# msxbreakout_slim.net
KiCad netlist of a schematic drawn in Altium Designer
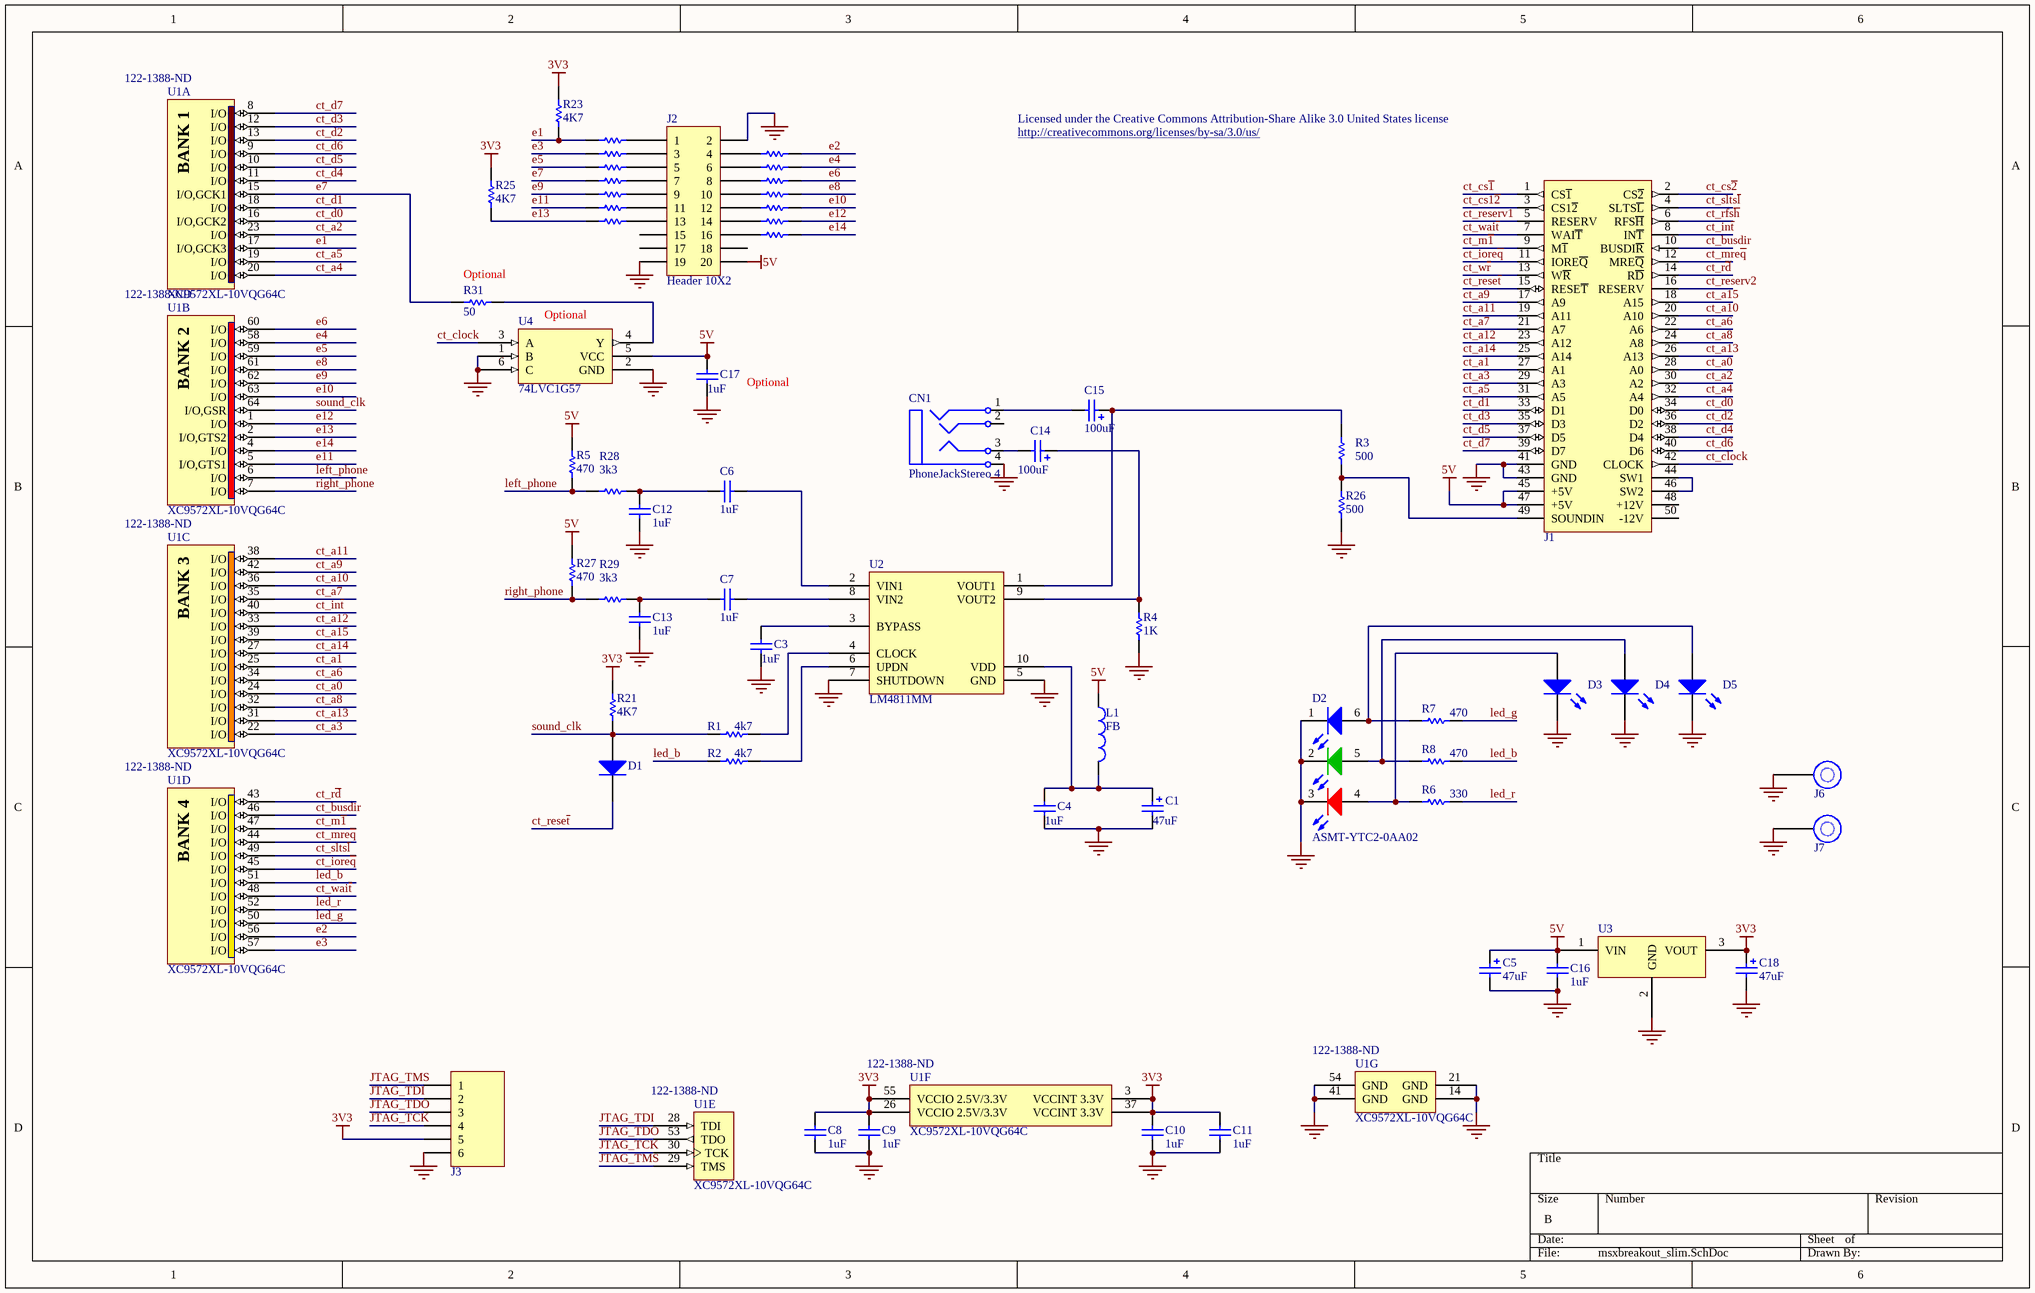
[diagram p0: msxbreakout_slim.SchDoc]

(export (version "E")
  (design (tool "Eeschema 10.0.6"))
  (components
    (comp (ref "C1")
      (value "47uF")
      (footprint "cap1210POL")
      (description "Polarized Capacitor")
      (fields (field (name "Comment") "Cap Pol1") (field (name "PUBLISHER") "Altium Limited"))
      (libsource (lib "msxarm") (part "Cap Pol1"))
    )
    (comp (ref "C3")
      (value "1uF")
      (footprint "cap0603")
      (description "Capacitor")
      (fields (field (name "Comment") "Cap") (field (name "PUBLISHER") "Altium Limited"))
      (libsource (lib "msxarm") (part "Cap"))
    )
    (comp (ref "C4")
      (value "1uF")
      (footprint "cap0603")
      (description "Capacitor")
      (fields (field (name "Comment") "Cap") (field (name "PUBLISHER") "Altium Limited"))
      (libsource (lib "msxarm") (part "Cap"))
    )
    (comp (ref "C5")
      (value "47uF")
      (footprint "cap1210POL")
      (description "Polarized Capacitor")
      (fields (field (name "Comment") "Cap Pol1") (field (name "PUBLISHER") "Altium Limited"))
      (libsource (lib "altium-import") (part "root_3_Cap Pol1_"))
    )
    (comp (ref "C6")
      (value "1uF")
      (footprint "cap0603")
      (description "Capacitor")
      (fields (field (name "Comment") "Cap") (field (name "PUBLISHER") "Altium Limited"))
      (libsource (lib "msxarm") (part "Cap"))
    )
    (comp (ref "C7")
      (value "1uF")
      (footprint "cap0603")
      (description "Capacitor")
      (fields (field (name "Comment") "Cap") (field (name "PUBLISHER") "Altium Limited"))
      (libsource (lib "msxarm") (part "Cap"))
    )
    (comp (ref "C8")
      (value "1uF")
      (footprint "cap0603")
      (description "Capacitor")
      (fields (field (name "Comment") "Cap") (field (name "PUBLISHER") "Altium Limited"))
      (libsource (lib "altium-import") (part "root_1_Cap_"))
    )
    (comp (ref "C9")
      (value "1uF")
      (footprint "cap0603")
      (description "Capacitor")
      (fields (field (name "Comment") "Cap") (field (name "PUBLISHER") "Altium Limited"))
      (libsource (lib "altium-import") (part "root_1_Cap_"))
    )
    (comp (ref "C10")
      (value "1uF")
      (footprint "cap0603")
      (description "Capacitor")
      (fields (field (name "Comment") "Cap") (field (name "PUBLISHER") "Altium Limited"))
      (libsource (lib "altium-import") (part "root_1_Cap_"))
    )
    (comp (ref "C11")
      (value "1uF")
      (footprint "cap0603")
      (description "Capacitor")
      (fields (field (name "Comment") "Cap") (field (name "PUBLISHER") "Altium Limited"))
      (libsource (lib "altium-import") (part "root_1_Cap_"))
    )
    (comp (ref "C12")
      (value "1uF")
      (footprint "cap0603")
      (description "Capacitor")
      (fields (field (name "Comment") "Cap") (field (name "PUBLISHER") "Altium Limited"))
      (libsource (lib "altium-import") (part "root_3_Cap_"))
    )
    (comp (ref "C13")
      (value "1uF")
      (footprint "cap0603")
      (description "Capacitor")
      (fields (field (name "Comment") "Cap") (field (name "PUBLISHER") "Altium Limited"))
      (libsource (lib "msxarm") (part "Cap"))
    )
    (comp (ref "C14")
      (value "100uF")
      (footprint "cap1210POL")
      (description "Polarized Capacitor")
      (fields (field (name "Comment") "Cap Pol1") (field (name "PUBLISHER") "Altium Limited"))
      (libsource (lib "msxarm") (part "Cap Pol1"))
    )
    (comp (ref "C15")
      (value "100uF")
      (footprint "cap1210POL")
      (description "Polarized Capacitor")
      (fields (field (name "Comment") "Cap Pol1") (field (name "PUBLISHER") "Altium Limited"))
      (libsource (lib "msxarm") (part "Cap Pol1"))
    )
    (comp (ref "C16")
      (value "1uF")
      (footprint "cap0603")
      (description "Capacitor")
      (fields (field (name "Comment") "Cap") (field (name "PUBLISHER") "Altium Limited"))
      (libsource (lib "msxarm") (part "Cap"))
    )
    (comp (ref "C17")
      (value "1uF")
      (footprint "cap0603")
      (description "Capacitor")
      (fields (field (name "Comment") "Cap") (field (name "PUBLISHER") "Altium Limited"))
      (libsource (lib "altium-import") (part "root_1_Cap_"))
    )
    (comp (ref "C18")
      (value "47uF")
      (footprint "cap1210POL")
      (description "Polarized Capacitor")
      (fields (field (name "Comment") "Cap Pol1") (field (name "PUBLISHER") "Altium Limited"))
      (libsource (lib "msxarm") (part "Cap Pol1"))
    )
    (comp (ref "CN1")
      (value "PhoneJackStereo 4")
      (footprint "SJ1-2503A")
      (libsource (lib "altium-import") (part "root_0_PhoneJackStereo4_"))
    )
    (comp (ref "D1")
      (value "Diode")
      (footprint "SOD323F")
      (description "Default Diode")
      (fields (field (name "PUBLISHER") "Altium Limited"))
      (libsource (lib "msxarm") (part "Diode"))
    )
    (comp (ref "D2")
      (value "ASMT-YTC2-0AA02")
      (footprint "ASMT-YTC2-0AA02")
      (description "Typical RED, GREEN, YELLOW, AMBER GaAs LED")
      (fields (field (name "PUBLISHER") "Altium Limited"))
      (libsource (lib "msxarm") (part "ASMT-YTC2-0AA02"))
    )
    (comp (ref "D3")
      (value "APA1606SURCK")
      (footprint "LED-0603_LAMP_RED")
      (description "1.6x0.6mm RIGHT ANGLE SMD CHIP LED LAMP, Hyper Red")
      (libsource (lib "altium-import") (part "root_3_APA1606SURCK_"))
    )
    (comp (ref "D4")
      (value "APA1606SURCK")
      (footprint "LED-0603_LAMP_GREEN")
      (description "1.6x0.6mm RIGHT ANGLE SMD CHIP LED LAMP, Hyper Red")
      (libsource (lib "altium-import") (part "root_3_APA1606SURCK_"))
    )
    (comp (ref "D5")
      (value "APA1606SURCK")
      (footprint "LED-0603_LAMP_BLUE")
      (description "1.6x0.6mm RIGHT ANGLE SMD CHIP LED LAMP, Hyper Red")
      (libsource (lib "altium-import") (part "root_3_APA1606SURCK_"))
    )
    (comp (ref "J1")
      (value "msxcart")
      (footprint "msxcart")
      (libsource (lib "altium-import") (part "root_0_msxcart_"))
    )
    (comp (ref "J2")
      (value "Header 10X2")
      (footprint "HDR2X10_90")
      (description "Header, 10-Pin, Dual row")
      (libsource (lib "altium-import") (part "root_0_Header 10X2_"))
    )
    (comp (ref "J3")
      (value "Header 1X6")
      (footprint "HDR1X6_90")
      (description "Header, 6-Pin, Single row")
      (libsource (lib "altium-import") (part "root_0_Header 1X6_"))
    )
    (comp (ref "J6")
      (value "MountHole")
      (footprint "MOUNTHOLE")
      (description "Mounting hole")
      (libsource (lib "msxarm") (part "MountHole"))
    )
    (comp (ref "J7")
      (value "MountHole")
      (footprint "MOUNTHOLE")
      (description "Mounting hole")
      (libsource (lib "msxarm") (part "MountHole"))
    )
    (comp (ref "L1")
      (value "FB")
      (footprint "ind1206")
      (description "Inductor")
      (fields (field (name "PUBLISHER") "Altium Limited"))
      (libsource (lib "altium-import") (part "root_3_Inductor_"))
    )
    (comp (ref "R1")
      (value "4k7")
      (footprint "res0603")
      (description "Resistor")
      (fields (field (name "Comment") "Res1") (field (name "PUBLISHER") "Altium Limited"))
      (libsource (lib "altium-import") (part "root_0_Res1_"))
    )
    (comp (ref "R2")
      (value "4k7")
      (footprint "msxbreakout:res0603")
      (description "Resistor")
      (fields (field (name "Comment") "Res1") (field (name "PUBLISHER") "Altium Limited"))
      (libsource (lib "altium-import") (part "root_0_Res1_"))
    )
    (comp (ref "R3")
      (value "500")
      (footprint "res0603")
      (description "Resistor")
      (fields (field (name "Comment") "Res1") (field (name "PUBLISHER") "Altium Limited"))
      (libsource (lib "altium-import") (part "root_1_Res1_"))
    )
    (comp (ref "R4")
      (value "1K")
      (footprint "res0603")
      (description "Resistor")
      (fields (field (name "Comment") "Res1") (field (name "PUBLISHER") "Altium Limited"))
      (libsource (lib "altium-import") (part "root_1_Res1_"))
    )
    (comp (ref "R5")
      (value "470")
      (footprint "msxbreakout:res0603")
      (description "Resistor")
      (fields (field (name "Comment") "Res1") (field (name "PUBLISHER") "Altium Limited"))
      (libsource (lib "altium-import") (part "root_1_Res1_"))
    )
    (comp (ref "R6")
      (value "330")
      (footprint "res0603")
      (description "Resistor")
      (fields (field (name "Comment") "Res1") (field (name "PUBLISHER") "Altium Limited"))
      (libsource (lib "altium-import") (part "root_0_Res1_"))
    )
    (comp (ref "R7")
      (value "470")
      (footprint "res0603")
      (description "Resistor")
      (fields (field (name "Comment") "Res1") (field (name "PUBLISHER") "Altium Limited"))
      (libsource (lib "altium-import") (part "root_0_Res1_"))
    )
    (comp (ref "R8")
      (value "470")
      (footprint "res0603")
      (description "Resistor")
      (fields (field (name "Comment") "Res1") (field (name "PUBLISHER") "Altium Limited"))
      (libsource (lib "altium-import") (part "root_0_Res1_"))
    )
    (comp (ref "R9")
      (value "Res1")
      (footprint "res0603")
      (description "Resistor")
      (fields (field (name "PUBLISHER") "Altium Limited"))
      (libsource (lib "altium-import") (part "root_0_Res1_"))
    )
    (comp (ref "R10")
      (value "Res1")
      (footprint "res0603")
      (description "Resistor")
      (fields (field (name "PUBLISHER") "Altium Limited"))
      (libsource (lib "altium-import") (part "root_0_Res1_"))
    )
    (comp (ref "R11")
      (value "Res1")
      (footprint "res0603")
      (description "Resistor")
      (fields (field (name "PUBLISHER") "Altium Limited"))
      (libsource (lib "altium-import") (part "root_0_Res1_"))
    )
    (comp (ref "R12")
      (value "Res1")
      (footprint "res0603")
      (description "Resistor")
      (fields (field (name "PUBLISHER") "Altium Limited"))
      (libsource (lib "altium-import") (part "root_0_Res1_"))
    )
    (comp (ref "R13")
      (value "Res1")
      (footprint "res0603")
      (description "Resistor")
      (fields (field (name "PUBLISHER") "Altium Limited"))
      (libsource (lib "altium-import") (part "root_0_Res1_"))
    )
    (comp (ref "R14")
      (value "Res1")
      (footprint "res0603")
      (description "Resistor")
      (fields (field (name "PUBLISHER") "Altium Limited"))
      (libsource (lib "altium-import") (part "root_0_Res1_"))
    )
    (comp (ref "R15")
      (value "Res1")
      (footprint "res0603")
      (description "Resistor")
      (fields (field (name "PUBLISHER") "Altium Limited"))
      (libsource (lib "altium-import") (part "root_0_Res1_"))
    )
    (comp (ref "R16")
      (value "Res1")
      (footprint "res0603")
      (description "Resistor")
      (fields (field (name "PUBLISHER") "Altium Limited"))
      (libsource (lib "altium-import") (part "root_0_Res1_"))
    )
    (comp (ref "R17")
      (value "Res1")
      (footprint "res0603")
      (description "Resistor")
      (fields (field (name "PUBLISHER") "Altium Limited"))
      (libsource (lib "altium-import") (part "root_0_Res1_"))
    )
    (comp (ref "R18")
      (value "Res1")
      (footprint "res0603")
      (description "Resistor")
      (fields (field (name "PUBLISHER") "Altium Limited"))
      (libsource (lib "altium-import") (part "root_0_Res1_"))
    )
    (comp (ref "R19")
      (value "Res1")
      (footprint "msxbreakout:res0603")
      (description "Resistor")
      (fields (field (name "PUBLISHER") "Altium Limited"))
      (libsource (lib "altium-import") (part "root_0_Res1_"))
    )
    (comp (ref "R20")
      (value "Res1")
      (footprint "res0603")
      (description "Resistor")
      (fields (field (name "PUBLISHER") "Altium Limited"))
      (libsource (lib "altium-import") (part "root_0_Res1_"))
    )
    (comp (ref "R21")
      (value "4K7")
      (footprint "msxbreakout:res0603")
      (description "Resistor")
      (fields (field (name "Comment") "Res1") (field (name "PUBLISHER") "Altium Limited"))
      (libsource (lib "altium-import") (part "root_1_Res1_"))
    )
    (comp (ref "R22")
      (value "Res1")
      (footprint "res0603")
      (description "Resistor")
      (fields (field (name "PUBLISHER") "Altium Limited"))
      (libsource (lib "altium-import") (part "root_0_Res1_"))
    )
    (comp (ref "R23")
      (value "4K7")
      (footprint "msxbreakout:res0603")
      (description "Resistor")
      (fields (field (name "Comment") "Res1") (field (name "PUBLISHER") "Altium Limited"))
      (libsource (lib "altium-import") (part "root_1_Res1_"))
    )
    (comp (ref "R24")
      (value "Res1")
      (footprint "res0603")
      (description "Resistor")
      (fields (field (name "PUBLISHER") "Altium Limited"))
      (libsource (lib "altium-import") (part "root_0_Res1_"))
    )
    (comp (ref "R25")
      (value "4K7")
      (footprint "res0603")
      (description "Resistor")
      (fields (field (name "Comment") "Res1") (field (name "PUBLISHER") "Altium Limited"))
      (libsource (lib "altium-import") (part "root_1_Res1_"))
    )
    (comp (ref "R26")
      (value "500")
      (footprint "res0603")
      (description "Resistor")
      (fields (field (name "Comment") "Res1") (field (name "PUBLISHER") "Altium Limited"))
      (libsource (lib "altium-import") (part "root_1_Res1_"))
    )
    (comp (ref "R27")
      (value "470")
      (footprint "msxbreakout:res0603")
      (description "Resistor")
      (fields (field (name "Comment") "Res1") (field (name "PUBLISHER") "Altium Limited"))
      (libsource (lib "altium-import") (part "root_1_Res1_"))
    )
    (comp (ref "R28")
      (value "3k3")
      (footprint "msxbreakout:res0603")
      (description "Resistor")
      (fields (field (name "Comment") "Res1") (field (name "PUBLISHER") "Altium Limited"))
      (libsource (lib "altium-import") (part "root_0_Res1_"))
    )
    (comp (ref "R29")
      (value "3k3")
      (footprint "msxbreakout:res0603")
      (description "Resistor")
      (fields (field (name "Comment") "Res1") (field (name "PUBLISHER") "Altium Limited"))
      (libsource (lib "altium-import") (part "root_0_Res1_"))
    )
    (comp (ref "R31")
      (value "50")
      (footprint "res0603")
      (description "Resistor")
      (fields (field (name "Comment") "Res1") (field (name "PUBLISHER") "Altium Limited"))
      (libsource (lib "altium-import") (part "root_0_Res1_"))
    )
    (comp (ref "U1")
      (value "XC9572XL-10VQG64C")
      (footprint "msxarm:VQG64_N")
      (fields (field (name "SUPPLIER PART NUMBER 1") "122-1388-ND"))
      (libsource (lib "msxarm") (part "XC9572XL-10VQG64C"))
    )
    (comp (ref "U2")
      (value "LM4811MM")
      (footprint "LM4811MM")
      (libsource (lib "altium-import") (part "root_0_LM4811MM_"))
    )
    (comp (ref "U3")
      (value "Regulator 3V3")
      (footprint "sot223_4")
      (libsource (lib "altium-import") (part "root_0_Regulator 3V3_"))
    )
    (comp (ref "U4")
      (value "74LVC1G57")
      (footprint "SOT-363 PKG")
      (libsource (lib "altium-import") (part "root_0_74LVC1G57_"))
    )
  )
  (nets
    (net (code "1") (name "/JTAG_TCK") (class "Default")
      (node (ref "J3") (pin "4") (pinfunction "4_4") (pintype "passive"))
      (node (ref "U1") (pin "30") (pinfunction "TCK_30") (pintype "input"))
    )
    (net (code "2") (name "/JTAG_TDI") (class "Default")
      (node (ref "J3") (pin "2") (pinfunction "2_2") (pintype "passive"))
      (node (ref "U1") (pin "28") (pinfunction "TDI_28") (pintype "input"))
    )
    (net (code "3") (name "/JTAG_TDO") (class "Default")
      (node (ref "J3") (pin "3") (pinfunction "3_3") (pintype "passive"))
      (node (ref "U1") (pin "53") (pinfunction "TDO_53") (pintype "output"))
    )
    (net (code "4") (name "/JTAG_TMS") (class "Default")
      (node (ref "J3") (pin "1") (pinfunction "1_1") (pintype "passive"))
      (node (ref "U1") (pin "29") (pinfunction "TMS_29") (pintype "input"))
    )
    (net (code "5") (name "/ct_a0") (class "Default")
      (node (ref "J1") (pin "28") (pinfunction "A0_28") (pintype "output"))
      (node (ref "U1") (pin "24") (pinfunction "I/O_24") (pintype "bidirectional"))
    )
    (net (code "6") (name "/ct_a1") (class "Default")
      (node (ref "J1") (pin "27") (pinfunction "A1_27") (pintype "output"))
      (node (ref "U1") (pin "25") (pinfunction "I/O_25") (pintype "bidirectional"))
    )
    (net (code "7") (name "/ct_a2") (class "Default")
      (node (ref "J1") (pin "30") (pinfunction "A2_30") (pintype "output"))
      (node (ref "U1") (pin "23") (pinfunction "I/O_23") (pintype "bidirectional"))
    )
    (net (code "8") (name "/ct_a3") (class "Default")
      (node (ref "J1") (pin "29") (pinfunction "A3_29") (pintype "output"))
      (node (ref "U1") (pin "22") (pinfunction "I/O_22") (pintype "bidirectional"))
    )
    (net (code "9") (name "/ct_a4") (class "Default")
      (node (ref "J1") (pin "32") (pinfunction "A4_32") (pintype "output"))
      (node (ref "U1") (pin "20") (pinfunction "I/O_20") (pintype "bidirectional"))
    )
    (net (code "10") (name "/ct_a5") (class "Default")
      (node (ref "J1") (pin "31") (pinfunction "A5_31") (pintype "output"))
      (node (ref "U1") (pin "19") (pinfunction "I/O_19") (pintype "bidirectional"))
    )
    (net (code "11") (name "/ct_a6") (class "Default")
      (node (ref "J1") (pin "22") (pinfunction "A6_22") (pintype "output"))
      (node (ref "U1") (pin "34") (pinfunction "I/O_34") (pintype "bidirectional"))
    )
    (net (code "12") (name "/ct_a7") (class "Default")
      (node (ref "J1") (pin "21") (pinfunction "A7_21") (pintype "output"))
      (node (ref "U1") (pin "35") (pinfunction "I/O_35") (pintype "bidirectional"))
    )
    (net (code "13") (name "/ct_a8") (class "Default")
      (node (ref "J1") (pin "24") (pinfunction "A8_24") (pintype "output"))
      (node (ref "U1") (pin "32") (pinfunction "I/O_32") (pintype "bidirectional"))
    )
    (net (code "14") (name "/ct_a9") (class "Default")
      (node (ref "J1") (pin "17") (pinfunction "A9_17") (pintype "output"))
      (node (ref "U1") (pin "42") (pinfunction "I/O_42") (pintype "bidirectional"))
    )
    (net (code "15") (name "/ct_a10") (class "Default")
      (node (ref "J1") (pin "20") (pinfunction "A10_20") (pintype "output"))
      (node (ref "U1") (pin "36") (pinfunction "I/O_36") (pintype "bidirectional"))
    )
    (net (code "16") (name "/ct_a11") (class "Default")
      (node (ref "J1") (pin "19") (pinfunction "A11_19") (pintype "output"))
      (node (ref "U1") (pin "38") (pinfunction "I/O_38") (pintype "bidirectional"))
    )
    (net (code "17") (name "/ct_a12") (class "Default")
      (node (ref "J1") (pin "23") (pinfunction "A12_23") (pintype "output"))
      (node (ref "U1") (pin "33") (pinfunction "I/O_33") (pintype "bidirectional"))
    )
    (net (code "18") (name "/ct_a13") (class "Default")
      (node (ref "J1") (pin "26") (pinfunction "A13_26") (pintype "output"))
      (node (ref "U1") (pin "31") (pinfunction "I/O_31") (pintype "bidirectional"))
    )
    (net (code "19") (name "/ct_a14") (class "Default")
      (node (ref "J1") (pin "25") (pinfunction "A14_25") (pintype "output"))
      (node (ref "U1") (pin "27") (pinfunction "I/O_27") (pintype "bidirectional"))
    )
    (net (code "20") (name "/ct_a15") (class "Default")
      (node (ref "J1") (pin "18") (pinfunction "A15_18") (pintype "output"))
      (node (ref "U1") (pin "39") (pinfunction "I/O_39") (pintype "bidirectional"))
    )
    (net (code "21") (name "/ct_busdir") (class "Default")
      (node (ref "J1") (pin "10") (pinfunction "BUSDI~{R}_10") (pintype "input"))
      (node (ref "U1") (pin "46") (pinfunction "I/O_46") (pintype "bidirectional"))
    )
    (net (code "22") (name "/ct_clock") (class "Default")
      (node (ref "J1") (pin "42") (pinfunction "CLOCK_42") (pintype "output"))
      (node (ref "U4") (pin "3") (pinfunction "A_3") (pintype "input"))
    )
    (net (code "23") (name "/ct_cs1~{2}") (class "Default")
      (node (ref "J1") (pin "3") (pinfunction "CS1~{2}_3") (pintype "output"))
    )
    (net (code "24") (name "/ct_cs~{1}") (class "Default")
      (node (ref "J1") (pin "1") (pinfunction "CS~{1}_1") (pintype "output"))
    )
    (net (code "25") (name "/ct_cs~{2}") (class "Default")
      (node (ref "J1") (pin "2") (pinfunction "CS~{2}_2") (pintype "output"))
    )
    (net (code "26") (name "/ct_d0") (class "Default")
      (node (ref "J1") (pin "34") (pinfunction "D0_34") (pintype "bidirectional"))
      (node (ref "U1") (pin "16") (pinfunction "I/O,GCK2_16") (pintype "bidirectional"))
    )
    (net (code "27") (name "/ct_d1") (class "Default")
      (node (ref "J1") (pin "33") (pinfunction "D1_33") (pintype "bidirectional"))
      (node (ref "U1") (pin "18") (pinfunction "I/O_18") (pintype "bidirectional"))
    )
    (net (code "28") (name "/ct_d2") (class "Default")
      (node (ref "J1") (pin "36") (pinfunction "D2_36") (pintype "bidirectional"))
      (node (ref "U1") (pin "13") (pinfunction "I/O_13") (pintype "bidirectional"))
    )
    (net (code "29") (name "/ct_d3") (class "Default")
      (node (ref "J1") (pin "35") (pinfunction "D3_35") (pintype "bidirectional"))
      (node (ref "U1") (pin "12") (pinfunction "I/O_12") (pintype "bidirectional"))
    )
    (net (code "30") (name "/ct_d4") (class "Default")
      (node (ref "J1") (pin "38") (pinfunction "D4_38") (pintype "bidirectional"))
      (node (ref "U1") (pin "11") (pinfunction "I/O_11") (pintype "bidirectional"))
    )
    (net (code "31") (name "/ct_d5") (class "Default")
      (node (ref "J1") (pin "37") (pinfunction "D5_37") (pintype "bidirectional"))
      (node (ref "U1") (pin "10") (pinfunction "I/O_10") (pintype "bidirectional"))
    )
    (net (code "32") (name "/ct_d6") (class "Default")
      (node (ref "J1") (pin "40") (pinfunction "D6_40") (pintype "bidirectional"))
      (node (ref "U1") (pin "9") (pinfunction "I/O_9") (pintype "bidirectional"))
    )
    (net (code "33") (name "/ct_d7") (class "Default")
      (node (ref "J1") (pin "39") (pinfunction "D7_39") (pintype "bidirectional"))
      (node (ref "U1") (pin "8") (pinfunction "I/O_8") (pintype "bidirectional"))
    )
    (net (code "34") (name "/ct_in~{t}") (class "Default")
      (node (ref "J1") (pin "8") (pinfunction "IN~{T}_8") (pintype "open_collector"))
      (node (ref "U1") (pin "40") (pinfunction "I/O_40") (pintype "bidirectional"))
    )
    (net (code "35") (name "/ct_iore~{q}") (class "Default")
      (node (ref "J1") (pin "11") (pinfunction "IORE~{Q}_11") (pintype "output"))
      (node (ref "U1") (pin "45") (pinfunction "I/O_45") (pintype "bidirectional"))
    )
    (net (code "36") (name "/ct_mre~{q}") (class "Default")
      (node (ref "J1") (pin "12") (pinfunction "MRE~{Q}_12") (pintype "output"))
      (node (ref "U1") (pin "44") (pinfunction "I/O_44") (pintype "bidirectional"))
    )
    (net (code "37") (name "/ct_m~{1}") (class "Default")
      (node (ref "J1") (pin "9") (pinfunction "M~{1}_9") (pintype "output"))
      (node (ref "U1") (pin "47") (pinfunction "I/O_47") (pintype "bidirectional"))
    )
    (net (code "38") (name "/ct_reserv1") (class "Default")
      (node (ref "J1") (pin "5") (pinfunction "RESERV_5") (pintype "tri_state"))
    )
    (net (code "39") (name "/ct_reserv2") (class "Default")
      (node (ref "J1") (pin "16") (pinfunction "RESERV_16") (pintype "passive"))
    )
    (net (code "40") (name "/ct_rese~{t}") (class "Default")
      (node (ref "D1") (pin "K") (pinfunction "K_K") (pintype "passive"))
      (node (ref "J1") (pin "15") (pinfunction "RESE~{T}_15") (pintype "bidirectional"))
    )
    (net (code "41") (name "/ct_rfs~{h}") (class "Default")
      (node (ref "J1") (pin "6") (pinfunction "RFS~{H}_6") (pintype "output"))
    )
    (net (code "42") (name "/ct_r~{d}") (class "Default")
      (node (ref "J1") (pin "14") (pinfunction "R~{D}_14") (pintype "output"))
      (node (ref "U1") (pin "43") (pinfunction "I/O_43") (pintype "bidirectional"))
    )
    (net (code "43") (name "/ct_slts~{l}") (class "Default")
      (node (ref "J1") (pin "4") (pinfunction "SLTS~{L}_4") (pintype "output"))
      (node (ref "U1") (pin "49") (pinfunction "I/O_49") (pintype "bidirectional"))
    )
    (net (code "44") (name "/ct_wai~{t}") (class "Default")
      (node (ref "J1") (pin "7") (pinfunction "WAI~{T}_7") (pintype "open_collector"))
      (node (ref "U1") (pin "48") (pinfunction "I/O_48") (pintype "bidirectional"))
    )
    (net (code "45") (name "/ct_w~{r}") (class "Default")
      (node (ref "J1") (pin "13") (pinfunction "W~{R}_13") (pintype "output"))
    )
    (net (code "46") (name "/e1") (class "Default")
      (node (ref "R23") (pin "1") (pinfunction "1_1") (pintype "passive"))
      (node (ref "R9") (pin "1") (pinfunction "1_1") (pintype "passive"))
      (node (ref "U1") (pin "17") (pinfunction "I/O,GCK3_17") (pintype "bidirectional"))
    )
    (net (code "47") (name "/e2") (class "Default")
      (node (ref "R11") (pin "2") (pinfunction "2_2") (pintype "passive"))
      (node (ref "U1") (pin "56") (pinfunction "I/O_56") (pintype "bidirectional"))
    )
    (net (code "48") (name "/e3") (class "Default")
      (node (ref "R10") (pin "1") (pinfunction "1_1") (pintype "passive"))
      (node (ref "U1") (pin "57") (pinfunction "I/O_57") (pintype "bidirectional"))
    )
    (net (code "49") (name "/e4") (class "Default")
      (node (ref "R13") (pin "2") (pinfunction "2_2") (pintype "passive"))
      (node (ref "U1") (pin "58") (pinfunction "I/O_58") (pintype "bidirectional"))
    )
    (net (code "50") (name "/e5") (class "Default")
      (node (ref "R12") (pin "1") (pinfunction "1_1") (pintype "passive"))
      (node (ref "U1") (pin "59") (pinfunction "I/O_59") (pintype "bidirectional"))
    )
    (net (code "51") (name "/e6") (class "Default")
      (node (ref "R15") (pin "2") (pinfunction "2_2") (pintype "passive"))
      (node (ref "U1") (pin "60") (pinfunction "I/O_60") (pintype "bidirectional"))
    )
    (net (code "52") (name "/e7") (class "Default")
      (node (ref "R14") (pin "1") (pinfunction "1_1") (pintype "passive"))
      (node (ref "R31") (pin "1") (pinfunction "1_1") (pintype "passive"))
      (node (ref "U1") (pin "15") (pinfunction "I/O,GCK1_15") (pintype "bidirectional"))
    )
    (net (code "53") (name "/e8") (class "Default")
      (node (ref "R18") (pin "2") (pinfunction "2_2") (pintype "passive"))
      (node (ref "U1") (pin "61") (pinfunction "I/O_61") (pintype "bidirectional"))
    )
    (net (code "54") (name "/e9") (class "Default")
      (node (ref "R16") (pin "1") (pinfunction "1_1") (pintype "passive"))
      (node (ref "U1") (pin "62") (pinfunction "I/O_62") (pintype "bidirectional"))
    )
    (net (code "55") (name "/e10") (class "Default")
      (node (ref "R20") (pin "2") (pinfunction "2_2") (pintype "passive"))
      (node (ref "U1") (pin "63") (pinfunction "I/O_63") (pintype "bidirectional"))
    )
    (net (code "56") (name "/e11") (class "Default")
      (node (ref "R17") (pin "1") (pinfunction "1_1") (pintype "passive"))
      (node (ref "U1") (pin "5") (pinfunction "I/O,GTS1_5") (pintype "bidirectional"))
    )
    (net (code "57") (name "/e12") (class "Default")
      (node (ref "R22") (pin "2") (pinfunction "2_2") (pintype "passive"))
      (node (ref "U1") (pin "1") (pinfunction "I/O_1") (pintype "bidirectional"))
    )
    (net (code "58") (name "/e13") (class "Default")
      (node (ref "R19") (pin "1") (pinfunction "1_1") (pintype "passive"))
      (node (ref "R25") (pin "1") (pinfunction "1_1") (pintype "passive"))
      (node (ref "U1") (pin "2") (pinfunction "I/O,GTS2_2") (pintype "bidirectional"))
    )
    (net (code "59") (name "/e14") (class "Default")
      (node (ref "R24") (pin "2") (pinfunction "2_2") (pintype "passive"))
      (node (ref "U1") (pin "4") (pinfunction "I/O_4") (pintype "bidirectional"))
    )
    (net (code "60") (name "/led_b") (class "Default")
      (node (ref "R2") (pin "1") (pinfunction "1_1") (pintype "passive"))
      (node (ref "R8") (pin "2") (pinfunction "2_2") (pintype "passive"))
      (node (ref "U1") (pin "51") (pinfunction "I/O_51") (pintype "bidirectional"))
    )
    (net (code "61") (name "/led_g") (class "Default")
      (node (ref "R7") (pin "2") (pinfunction "2_2") (pintype "passive"))
      (node (ref "U1") (pin "50") (pinfunction "I/O_50") (pintype "bidirectional"))
    )
    (net (code "62") (name "/led_r") (class "Default")
      (node (ref "R6") (pin "2") (pinfunction "2_2") (pintype "passive"))
      (node (ref "U1") (pin "52") (pinfunction "I/O_52") (pintype "bidirectional"))
    )
    (net (code "63") (name "/left_phone") (class "Default")
      (node (ref "R28") (pin "1") (pinfunction "1_1") (pintype "passive"))
      (node (ref "R5") (pin "1") (pinfunction "1_1") (pintype "passive"))
      (node (ref "U1") (pin "6") (pinfunction "I/O_6") (pintype "bidirectional"))
    )
    (net (code "64") (name "/right_phone") (class "Default")
      (node (ref "R27") (pin "1") (pinfunction "1_1") (pintype "passive"))
      (node (ref "R29") (pin "1") (pinfunction "1_1") (pintype "passive"))
      (node (ref "U1") (pin "7") (pinfunction "I/O_7") (pintype "bidirectional"))
    )
    (net (code "65") (name "/sound_clk") (class "Default")
      (node (ref "D1") (pin "A") (pinfunction "A_A") (pintype "passive"))
      (node (ref "R1") (pin "1") (pinfunction "1_1") (pintype "passive"))
      (node (ref "R21") (pin "1") (pinfunction "1_1") (pintype "passive"))
      (node (ref "U1") (pin "64") (pinfunction "I/O,GSR_64") (pintype "bidirectional"))
    )
    (net (code "66") (name "3V3") (class "Default")
      (node (ref "C10") (pin "2") (pinfunction "2_2") (pintype "passive"))
      (node (ref "C11") (pin "2") (pinfunction "2_2") (pintype "passive"))
      (node (ref "C18") (pin "1") (pinfunction "1_1") (pintype "passive"))
      (node (ref "C8") (pin "2") (pinfunction "2_2") (pintype "passive"))
      (node (ref "C9") (pin "2") (pinfunction "2_2") (pintype "passive"))
      (node (ref "J3") (pin "5") (pinfunction "5_5") (pintype "passive"))
      (node (ref "R21") (pin "2") (pinfunction "2_2") (pintype "passive"))
      (node (ref "R23") (pin "2") (pinfunction "2_2") (pintype "passive"))
      (node (ref "R25") (pin "2") (pinfunction "2_2") (pintype "passive"))
      (node (ref "U1") (pin "26") (pinfunction "VCCIO_2.5V/3.3V_26") (pintype "power_in"))
      (node (ref "U1") (pin "3") (pinfunction "VCCINT_3.3V_3") (pintype "power_in"))
      (node (ref "U1") (pin "37") (pinfunction "VCCINT_3.3V_37") (pintype "power_in"))
      (node (ref "U1") (pin "55") (pinfunction "VCCIO_2.5V/3.3V_55") (pintype "power_in"))
      (node (ref "U3") (pin "3") (pinfunction "VOUT_3") (pintype "passive"))
    )
    (net (code "67") (name "5V") (class "Default")
      (node (ref "C16") (pin "2") (pinfunction "2_2") (pintype "passive"))
      (node (ref "C17") (pin "2") (pinfunction "2_2") (pintype "passive"))
      (node (ref "C5") (pin "1") (pinfunction "1_1") (pintype "passive"))
      (node (ref "J1") (pin "45") (pinfunction "+5V_45") (pintype "power_in"))
      (node (ref "J1") (pin "47") (pinfunction "+5V_47") (pintype "power_in"))
      (node (ref "J2") (pin "20") (pinfunction "20_20") (pintype "passive"))
      (node (ref "L1") (pin "1") (pinfunction "1_1") (pintype "passive"))
      (node (ref "R27") (pin "2") (pinfunction "2_2") (pintype "passive"))
      (node (ref "R5") (pin "2") (pinfunction "2_2") (pintype "passive"))
      (node (ref "U3") (pin "1") (pinfunction "VIN_1") (pintype "passive"))
      (node (ref "U4") (pin "5") (pinfunction "VCC_5") (pintype "power_in"))
    )
    (net (code "68") (name "GND") (class "Default")
      (node (ref "C1") (pin "2") (pinfunction "2_2") (pintype "passive"))
      (node (ref "C10") (pin "1") (pinfunction "1_1") (pintype "passive"))
      (node (ref "C11") (pin "1") (pinfunction "1_1") (pintype "passive"))
      (node (ref "C12") (pin "2") (pinfunction "2_2") (pintype "passive"))
      (node (ref "C13") (pin "2") (pinfunction "2_2") (pintype "passive"))
      (node (ref "C16") (pin "1") (pinfunction "1_1") (pintype "passive"))
      (node (ref "C17") (pin "1") (pinfunction "1_1") (pintype "passive"))
      (node (ref "C18") (pin "2") (pinfunction "2_2") (pintype "passive"))
      (node (ref "C3") (pin "1") (pinfunction "1_1") (pintype "passive"))
      (node (ref "C4") (pin "1") (pinfunction "1_1") (pintype "passive"))
      (node (ref "C5") (pin "2") (pinfunction "2_2") (pintype "passive"))
      (node (ref "C8") (pin "1") (pinfunction "1_1") (pintype "passive"))
      (node (ref "C9") (pin "1") (pinfunction "1_1") (pintype "passive"))
      (node (ref "CN1") (pin "4") (pinfunction "4_4") (pintype "passive"))
      (node (ref "D2") (pin "1") (pinfunction "1_1") (pintype "passive"))
      (node (ref "D2") (pin "2") (pinfunction "2_2") (pintype "passive"))
      (node (ref "D2") (pin "3") (pinfunction "3_3") (pintype "passive"))
      (node (ref "D3") (pin "2") (pinfunction "K_2") (pintype "passive"))
      (node (ref "D4") (pin "2") (pinfunction "K_2") (pintype "passive"))
      (node (ref "D5") (pin "2") (pinfunction "K_2") (pintype "passive"))
      (node (ref "J1") (pin "41") (pinfunction "GND_41") (pintype "power_in"))
      (node (ref "J1") (pin "43") (pinfunction "GND_43") (pintype "power_in"))
      (node (ref "J2") (pin "19") (pinfunction "19_19") (pintype "passive"))
      (node (ref "J2") (pin "2") (pinfunction "2_2") (pintype "passive"))
      (node (ref "J3") (pin "6") (pinfunction "6_6") (pintype "passive"))
      (node (ref "J6") (pin "1") (pinfunction "1_1") (pintype "passive"))
      (node (ref "J7") (pin "1") (pinfunction "1_1") (pintype "passive"))
      (node (ref "R26") (pin "1") (pinfunction "1_1") (pintype "passive"))
      (node (ref "R4") (pin "1") (pinfunction "1_1") (pintype "passive"))
      (node (ref "U1") (pin "14") (pinfunction "GND_14") (pintype "power_in"))
      (node (ref "U1") (pin "21") (pinfunction "GND_21") (pintype "power_in"))
      (node (ref "U1") (pin "41") (pinfunction "GND_41") (pintype "power_in"))
      (node (ref "U1") (pin "54") (pinfunction "GND_54") (pintype "power_in"))
      (node (ref "U2") (pin "5") (pinfunction "GND_5") (pintype "passive"))
      (node (ref "U2") (pin "7") (pinfunction "SHUTDOWN_7") (pintype "passive"))
      (node (ref "U3") (pin "2") (pinfunction "GND_2") (pintype "passive"))
      (node (ref "U4") (pin "1") (pinfunction "B_1") (pintype "input"))
      (node (ref "U4") (pin "2") (pinfunction "GND_2") (pintype "power_in"))
      (node (ref "U4") (pin "6") (pinfunction "C_6") (pintype "input"))
    )
    (net (code "69") (name "Net-(C12-Pad1)") (class "Default")
      (node (ref "C12") (pin "1") (pinfunction "1_1") (pintype "passive"))
      (node (ref "C6") (pin "2") (pinfunction "2_2") (pintype "passive"))
      (node (ref "R28") (pin "2") (pinfunction "2_2") (pintype "passive"))
    )
    (net (code "70") (name "Net-(C13-Pad1)") (class "Default")
      (node (ref "C13") (pin "1") (pinfunction "1_1") (pintype "passive"))
      (node (ref "C7") (pin "2") (pinfunction "2_2") (pintype "passive"))
      (node (ref "R29") (pin "2") (pinfunction "2_2") (pintype "passive"))
    )
    (net (code "71") (name "Net-(C14-Pad2)") (class "Default")
      (node (ref "C14") (pin "2") (pinfunction "2_2") (pintype "passive"))
      (node (ref "CN1") (pin "3") (pinfunction "3_3") (pintype "passive"))
    )
    (net (code "72") (name "Net-(C15-Pad2)") (class "Default")
      (node (ref "C15") (pin "2") (pinfunction "2_2") (pintype "passive"))
      (node (ref "CN1") (pin "1") (pinfunction "1_1") (pintype "passive"))
    )
    (net (code "73") (name "Net-(D3-A)") (class "Default")
      (node (ref "D2") (pin "4") (pinfunction "4_4") (pintype "passive"))
      (node (ref "D3") (pin "1") (pinfunction "A_1") (pintype "passive"))
      (node (ref "R6") (pin "1") (pinfunction "1_1") (pintype "passive"))
    )
    (net (code "74") (name "Net-(D4-A)") (class "Default")
      (node (ref "D2") (pin "5") (pinfunction "5_5") (pintype "passive"))
      (node (ref "D4") (pin "1") (pinfunction "A_1") (pintype "passive"))
      (node (ref "R8") (pin "1") (pinfunction "1_1") (pintype "passive"))
    )
    (net (code "75") (name "Net-(D5-A)") (class "Default")
      (node (ref "D2") (pin "6") (pinfunction "6_6") (pintype "passive"))
      (node (ref "D5") (pin "1") (pinfunction "A_1") (pintype "passive"))
      (node (ref "R7") (pin "1") (pinfunction "1_1") (pintype "passive"))
    )
    (net (code "76") (name "Net-(J1-SOUNDIN)") (class "Default")
      (node (ref "J1") (pin "49") (pinfunction "SOUNDIN_49") (pintype "passive"))
      (node (ref "R26") (pin "2") (pinfunction "2_2") (pintype "passive"))
      (node (ref "R3") (pin "1") (pinfunction "1_1") (pintype "passive"))
    )
    (net (code "77") (name "Net-(J1-SW1)") (class "Default")
      (node (ref "J1") (pin "44") (pinfunction "SW1_44") (pintype "passive"))
      (node (ref "J1") (pin "46") (pinfunction "SW2_46") (pintype "passive"))
    )
    (net (code "78") (name "Net-(J2-Pad1)") (class "Default")
      (node (ref "J2") (pin "1") (pinfunction "1_1") (pintype "passive"))
      (node (ref "R9") (pin "2") (pinfunction "2_2") (pintype "passive"))
    )
    (net (code "79") (name "Net-(J2-Pad3)") (class "Default")
      (node (ref "J2") (pin "3") (pinfunction "3_3") (pintype "passive"))
      (node (ref "R10") (pin "2") (pinfunction "2_2") (pintype "passive"))
    )
    (net (code "80") (name "Net-(J2-Pad4)") (class "Default")
      (node (ref "J2") (pin "4") (pinfunction "4_4") (pintype "passive"))
      (node (ref "R11") (pin "1") (pinfunction "1_1") (pintype "passive"))
    )
    (net (code "81") (name "Net-(J2-Pad5)") (class "Default")
      (node (ref "J2") (pin "5") (pinfunction "5_5") (pintype "passive"))
      (node (ref "R12") (pin "2") (pinfunction "2_2") (pintype "passive"))
    )
    (net (code "82") (name "Net-(J2-Pad6)") (class "Default")
      (node (ref "J2") (pin "6") (pinfunction "6_6") (pintype "passive"))
      (node (ref "R13") (pin "1") (pinfunction "1_1") (pintype "passive"))
    )
    (net (code "83") (name "Net-(J2-Pad7)") (class "Default")
      (node (ref "J2") (pin "7") (pinfunction "7_7") (pintype "passive"))
      (node (ref "R14") (pin "2") (pinfunction "2_2") (pintype "passive"))
    )
    (net (code "84") (name "Net-(J2-Pad8)") (class "Default")
      (node (ref "J2") (pin "8") (pinfunction "8_8") (pintype "passive"))
      (node (ref "R15") (pin "1") (pinfunction "1_1") (pintype "passive"))
    )
    (net (code "85") (name "Net-(J2-Pad9)") (class "Default")
      (node (ref "J2") (pin "9") (pinfunction "9_9") (pintype "passive"))
      (node (ref "R16") (pin "2") (pinfunction "2_2") (pintype "passive"))
    )
    (net (code "86") (name "Net-(J2-Pad10)") (class "Default")
      (node (ref "J2") (pin "10") (pinfunction "10_10") (pintype "passive"))
      (node (ref "R18") (pin "1") (pinfunction "1_1") (pintype "passive"))
    )
    (net (code "87") (name "Net-(J2-Pad11)") (class "Default")
      (node (ref "J2") (pin "11") (pinfunction "11_11") (pintype "passive"))
      (node (ref "R17") (pin "2") (pinfunction "2_2") (pintype "passive"))
    )
    (net (code "88") (name "Net-(J2-Pad12)") (class "Default")
      (node (ref "J2") (pin "12") (pinfunction "12_12") (pintype "passive"))
      (node (ref "R20") (pin "1") (pinfunction "1_1") (pintype "passive"))
    )
    (net (code "89") (name "Net-(J2-Pad13)") (class "Default")
      (node (ref "J2") (pin "13") (pinfunction "13_13") (pintype "passive"))
      (node (ref "R19") (pin "2") (pinfunction "2_2") (pintype "passive"))
    )
    (net (code "90") (name "Net-(J2-Pad14)") (class "Default")
      (node (ref "J2") (pin "14") (pinfunction "14_14") (pintype "passive"))
      (node (ref "R22") (pin "1") (pinfunction "1_1") (pintype "passive"))
    )
    (net (code "91") (name "Net-(J2-Pad16)") (class "Default")
      (node (ref "J2") (pin "16") (pinfunction "16_16") (pintype "passive"))
      (node (ref "R24") (pin "1") (pinfunction "1_1") (pintype "passive"))
    )
    (net (code "92") (name "Net-(U2-BYPASS)") (class "Default")
      (node (ref "C3") (pin "2") (pinfunction "2_2") (pintype "passive"))
      (node (ref "U2") (pin "3") (pinfunction "BYPASS_3") (pintype "passive"))
    )
    (net (code "93") (name "Net-(U2-CLOCK)") (class "Default")
      (node (ref "R1") (pin "2") (pinfunction "2_2") (pintype "passive"))
      (node (ref "U2") (pin "4") (pinfunction "CLOCK_4") (pintype "passive"))
    )
    (net (code "94") (name "Net-(U2-UPDN)") (class "Default")
      (node (ref "R2") (pin "2") (pinfunction "2_2") (pintype "passive"))
      (node (ref "U2") (pin "6") (pinfunction "UPDN_6") (pintype "passive"))
    )
    (net (code "95") (name "Net-(U2-VDD)") (class "Default")
      (node (ref "C1") (pin "1") (pinfunction "1_1") (pintype "passive"))
      (node (ref "C4") (pin "2") (pinfunction "2_2") (pintype "passive"))
      (node (ref "L1") (pin "2") (pinfunction "2_2") (pintype "passive"))
      (node (ref "U2") (pin "10") (pinfunction "VDD_10") (pintype "passive"))
    )
    (net (code "96") (name "Net-(U2-VIN1)") (class "Default")
      (node (ref "C6") (pin "1") (pinfunction "1_1") (pintype "passive"))
      (node (ref "U2") (pin "2") (pinfunction "VIN1_2") (pintype "passive"))
    )
    (net (code "97") (name "Net-(U2-VIN2)") (class "Default")
      (node (ref "C7") (pin "1") (pinfunction "1_1") (pintype "passive"))
      (node (ref "U2") (pin "8") (pinfunction "VIN2_8") (pintype "passive"))
    )
    (net (code "98") (name "Net-(U2-VOUT1)") (class "Default")
      (node (ref "C15") (pin "1") (pinfunction "1_1") (pintype "passive"))
      (node (ref "R3") (pin "2") (pinfunction "2_2") (pintype "passive"))
      (node (ref "U2") (pin "1") (pinfunction "VOUT1_1") (pintype "passive"))
    )
    (net (code "99") (name "Net-(U2-VOUT2)") (class "Default")
      (node (ref "C14") (pin "1") (pinfunction "1_1") (pintype "passive"))
      (node (ref "R4") (pin "2") (pinfunction "2_2") (pintype "passive"))
      (node (ref "U2") (pin "9") (pinfunction "VOUT2_9") (pintype "passive"))
    )
    (net (code "100") (name "Net-(U4-Y)") (class "Default")
      (node (ref "R31") (pin "2") (pinfunction "2_2") (pintype "passive"))
      (node (ref "U4") (pin "4") (pinfunction "Y_4") (pintype "output"))
    )
    (net (code "101") (name "unconnected-(CN1-Pad2)") (class "Default")
      (node (ref "CN1") (pin "2") (pinfunction "2_2") (pintype "passive"))
    )
    (net (code "102") (name "unconnected-(J1-+12V-Pad48)") (class "Default")
      (node (ref "J1") (pin "48") (pinfunction "+12V_48") (pintype "power_in"))
    )
    (net (code "103") (name "unconnected-(J1--12V-Pad50)") (class "Default")
      (node (ref "J1") (pin "50") (pinfunction "-12V_50") (pintype "power_in"))
    )
    (net (code "104") (name "unconnected-(J2-Pad15)") (class "Default")
      (node (ref "J2") (pin "15") (pinfunction "15_15") (pintype "passive"))
    )
    (net (code "105") (name "unconnected-(J2-Pad17)") (class "Default")
      (node (ref "J2") (pin "17") (pinfunction "17_17") (pintype "passive"))
    )
    (net (code "106") (name "unconnected-(J2-Pad18)") (class "Default")
      (node (ref "J2") (pin "18") (pinfunction "18_18") (pintype "passive"))
    )
  )
)
